# KHKT25.net
KiCad netlist of a schematic drawn in Altium Designer
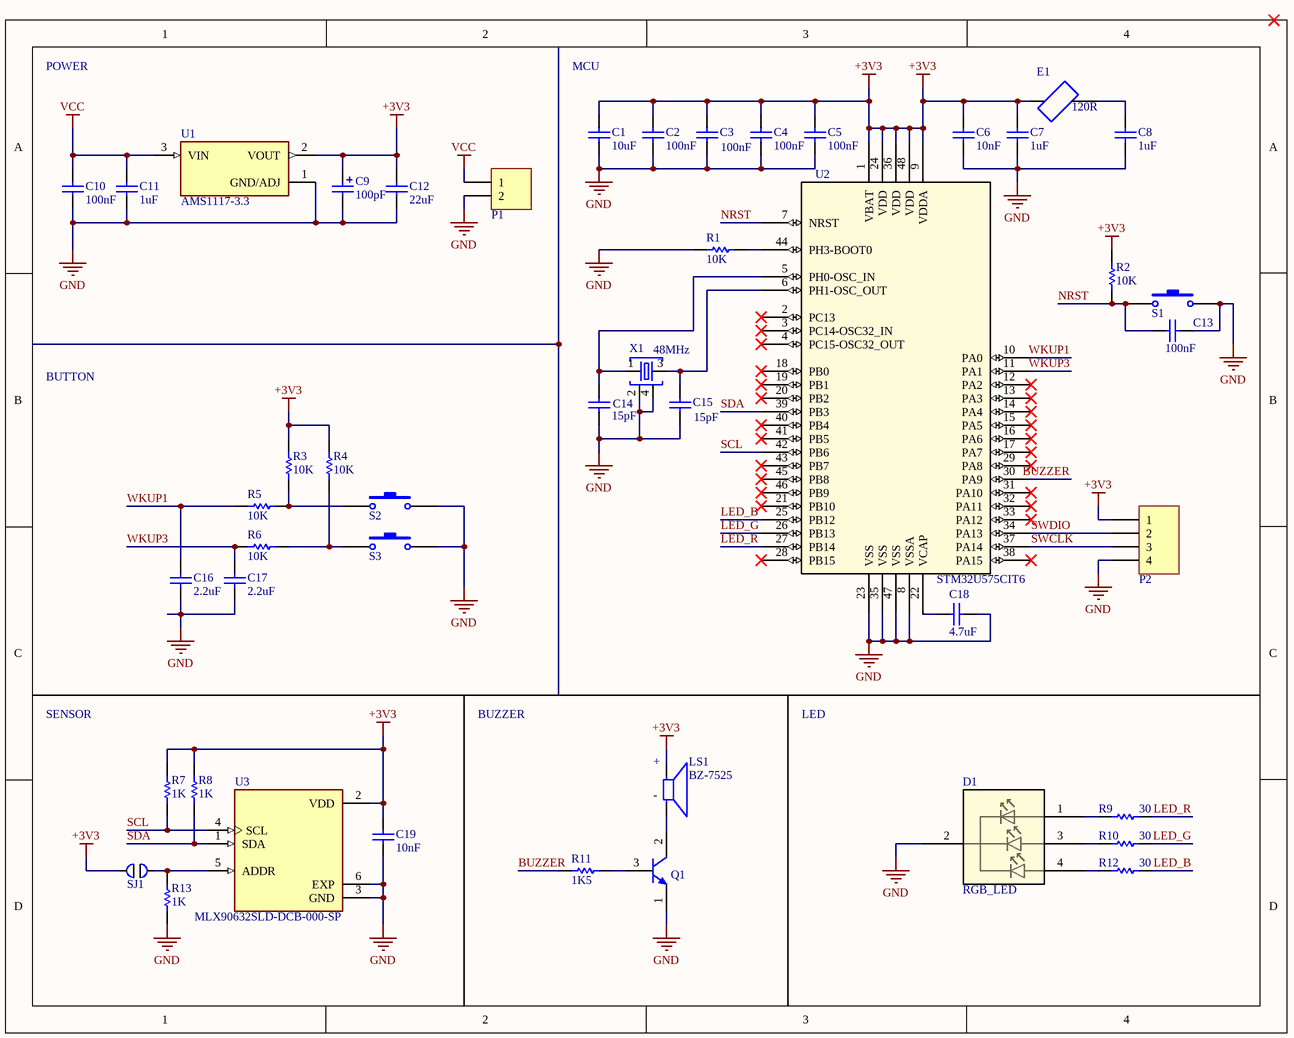
[diagram p0: KHKT25.SchDoc]

(export (version "E")
  (design (tool "Eeschema 10.0.6"))
  (components
    (comp (ref "C1")
      (value "10uF")
      (footprint "CAP-SM-0603")
      (description "Capacitor")
      (fields (field (name "Comment") "Cap Non-Pol SMD"))
      (libsource (lib "PIF_Library") (part "Cap Non-Pol SMD"))
    )
    (comp (ref "C2")
      (value "100nF")
      (footprint "CAP-SM-0603")
      (description "Capacitor")
      (fields (field (name "Comment") "Cap Non-Pol SMD"))
      (libsource (lib "PIF_Library") (part "Cap Non-Pol SMD"))
    )
    (comp (ref "C3")
      (value "100nF")
      (footprint "CAP-SM-0603")
      (description "Capacitor")
      (fields (field (name "Comment") "Cap Non-Pol SMD"))
      (libsource (lib "PIF_Library") (part "Cap Non-Pol SMD"))
    )
    (comp (ref "C4")
      (value "100nF")
      (footprint "CAP-SM-0603")
      (description "Capacitor")
      (fields (field (name "Comment") "Cap Non-Pol SMD"))
      (libsource (lib "PIF_Library") (part "Cap Non-Pol SMD"))
    )
    (comp (ref "C5")
      (value "100nF")
      (footprint "CAP-SM-0603")
      (description "Capacitor")
      (fields (field (name "Comment") "Cap Non-Pol SMD"))
      (libsource (lib "PIF_Library") (part "Cap Non-Pol SMD"))
    )
    (comp (ref "C6")
      (value "10nF")
      (footprint "CAP-SM-0603")
      (description "Capacitor")
      (fields (field (name "Comment") "Cap Non-Pol SMD"))
      (libsource (lib "PIF_Library") (part "Cap Non-Pol SMD"))
    )
    (comp (ref "C7")
      (value "1uF")
      (footprint "CAP-SM-0603")
      (description "Capacitor")
      (fields (field (name "Comment") "Cap Non-Pol SMD"))
      (libsource (lib "PIF_Library") (part "Cap Non-Pol SMD"))
    )
    (comp (ref "C8")
      (value "1uF")
      (footprint "CAP-SM-0603")
      (description "Capacitor")
      (fields (field (name "Comment") "Cap Non-Pol SMD"))
      (libsource (lib "PIF_Library") (part "Cap Non-Pol SMD"))
    )
    (comp (ref "C9")
      (value "100pF")
      (footprint "CAP ALU SIZE B")
      (description "Polarized Capacitor (Radial)")
      (fields (field (name "Comment") "Cap Pol SMD"))
      (libsource (lib "PIF_Library") (part "Cap Pol SMD"))
    )
    (comp (ref "C10")
      (value "100nF")
      (footprint "CAP-SM-0603")
      (description "Capacitor")
      (fields (field (name "Comment") "Cap Non-Pol SMD"))
      (libsource (lib "PIF_Library") (part "Cap Non-Pol SMD"))
    )
    (comp (ref "C11")
      (value "1uF")
      (footprint "CAP-SM-0603")
      (description "Capacitor")
      (fields (field (name "Comment") "Cap Non-Pol SMD"))
      (libsource (lib "PIF_Library") (part "Cap Non-Pol SMD"))
    )
    (comp (ref "C12")
      (value "22uF")
      (footprint "CAP-SM-0603")
      (description "Capacitor")
      (fields (field (name "Comment") "Cap Non-Pol SMD"))
      (libsource (lib "PIF_Library") (part "Cap Non-Pol SMD"))
    )
    (comp (ref "C13")
      (value "100nF")
      (footprint "CAP-SM-0603")
      (description "Capacitor")
      (fields (field (name "Comment") "Cap Non-Pol SMD"))
      (libsource (lib "PIF_Library") (part "Cap Non-Pol SMD"))
    )
    (comp (ref "C14")
      (value "15pF")
      (footprint "CAP-SM-0603")
      (description "Capacitor")
      (fields (field (name "Comment") "Cap Non-Pol SMD"))
      (libsource (lib "PIF_Library") (part "Cap Non-Pol SMD"))
    )
    (comp (ref "C15")
      (value "15pF")
      (footprint "CAP-SM-0603")
      (description "Capacitor")
      (fields (field (name "Comment") "Cap Non-Pol SMD"))
      (libsource (lib "PIF_Library") (part "Cap Non-Pol SMD"))
    )
    (comp (ref "C16")
      (value "2.2uF")
      (footprint "CAP-SM-0603")
      (description "Capacitor")
      (fields (field (name "Comment") "Cap Non-Pol SMD"))
      (libsource (lib "PIF_Library") (part "Cap Non-Pol SMD"))
    )
    (comp (ref "C17")
      (value "2.2uF")
      (footprint "CAP-SM-0603")
      (description "Capacitor")
      (fields (field (name "Comment") "Cap Non-Pol SMD"))
      (libsource (lib "PIF_Library") (part "Cap Non-Pol SMD"))
    )
    (comp (ref "C18")
      (value "4.7uF")
      (footprint "CAP-SM-0603")
      (description "Capacitor")
      (fields (field (name "Comment") "Cap Non-Pol SMD"))
      (libsource (lib "PIF_Library") (part "Cap Non-Pol SMD"))
    )
    (comp (ref "C19")
      (value "10nF")
      (footprint "CAP-SM-0603")
      (description "Capacitor")
      (fields (field (name "Comment") "Cap Non-Pol SMD"))
      (libsource (lib "PIF_Library") (part "Cap Non-Pol SMD"))
    )
    (comp (ref "D1")
      (value "RGB_LED")
      (footprint "RGB_LED")
      (description "Description")
      (fields
        (field (name "MANUFACTURER_PART_NUMBER") "L-154A4SURKQBDZGW")
        (field (name "COPYRIGHT") "Copyright (C) 2025 Ultra Librarian. All rights reserved.")
      )
      (libsource (lib "IntLib") (part "RGB_LED"))
    )
    (comp (ref "E1")
      (value "120R")
      (footprint "FB_MI0805K400R-10")
      (fields (field (name "MF") "Laird-Signal Integrity Products") (field (name "MP") "MI0805K400R-10"))
      (libsource (lib "IntLib") (part "MI0805K400R-10"))
    )
    (comp (ref "LS1")
      (value "BZ-7525")
      (footprint "XDCCMT-7525")
      (description "7.5 mm, 3.6 Vo-p, 80 dB, Surface Mount (SMT), Magnetic Audio Transducer Buzzer")
      (fields (field (name "MF") "Same Sky") (field (name "MP") "CMT-7525-80-SMT-TR"))
      (libsource (lib "IntLib") (part "BZ-7525"))
    )
    (comp (ref "P1")
      (value "Header 2")
      (footprint "JP2")
      (description "Header, 2-Pin")
      (fields (field (name "PUBLISHER") "Altium Limited"))
      (libsource (lib "PIF_Library") (part "Header 2"))
    )
    (comp (ref "P2")
      (value "Header 4H")
      (footprint "JP4H")
      (description "Header, 4-Pin, Right Angle")
      (fields (field (name "PUBLISHER") "Altium Limited"))
      (libsource (lib "PIF_Library") (part "Header 4H"))
    )
    (comp (ref "Q1")
      (value "C1815")
      (footprint "QTO-92")
      (description "NPN Bipolar Transistor")
      (libsource (lib "PIF_Library") (part "C1815"))
    )
    (comp (ref "R1")
      (value "10K")
      (footprint "RES-SM-0603")
      (description "Resistor")
      (fields (field (name "Comment") "RESISTOR SMD"))
      (libsource (lib "PIF_Library") (part "RESISTOR SMD"))
    )
    (comp (ref "R2")
      (value "10K")
      (footprint "RES-SM-0603")
      (description "Resistor")
      (fields (field (name "Comment") "RESISTOR SMD"))
      (libsource (lib "PIF_Library") (part "RESISTOR SMD"))
    )
    (comp (ref "R3")
      (value "10K")
      (footprint "RES-SM-0603")
      (description "Resistor")
      (fields (field (name "Comment") "RESISTOR SMD"))
      (libsource (lib "PIF_Library") (part "RESISTOR SMD"))
    )
    (comp (ref "R4")
      (value "10K")
      (footprint "RES-SM-0603")
      (description "Resistor")
      (fields (field (name "Comment") "RESISTOR SMD"))
      (libsource (lib "PIF_Library") (part "RESISTOR SMD"))
    )
    (comp (ref "R5")
      (value "10K")
      (footprint "RES-SM-0603")
      (description "Resistor")
      (fields (field (name "Comment") "RESISTOR SMD"))
      (libsource (lib "PIF_Library") (part "RESISTOR SMD"))
    )
    (comp (ref "R6")
      (value "10K")
      (footprint "RES-SM-0603")
      (description "Resistor")
      (fields (field (name "Comment") "RESISTOR SMD"))
      (libsource (lib "PIF_Library") (part "RESISTOR SMD"))
    )
    (comp (ref "R7")
      (value "1K")
      (footprint "RES-SM-0603")
      (description "Resistor")
      (fields (field (name "Comment") "RESISTOR SMD"))
      (libsource (lib "PIF_Library") (part "RESISTOR SMD"))
    )
    (comp (ref "R8")
      (value "1K")
      (footprint "RES-SM-0603")
      (description "Resistor")
      (fields (field (name "Comment") "RESISTOR SMD"))
      (libsource (lib "PIF_Library") (part "RESISTOR SMD"))
    )
    (comp (ref "R9")
      (value "30")
      (footprint "RES-SM-0603")
      (description "Resistor")
      (fields (field (name "Comment") "RESISTOR SMD"))
      (libsource (lib "PIF_Library") (part "RESISTOR SMD"))
    )
    (comp (ref "R10")
      (value "30")
      (footprint "RES-SM-0603")
      (description "Resistor")
      (fields (field (name "Comment") "RESISTOR SMD"))
      (libsource (lib "PIF_Library") (part "RESISTOR SMD"))
    )
    (comp (ref "R11")
      (value "1K5")
      (footprint "RES-SM-0603")
      (description "Resistor")
      (fields (field (name "Comment") "RESISTOR SMD"))
      (libsource (lib "PIF_Library") (part "RESISTOR SMD"))
    )
    (comp (ref "R12")
      (value "30")
      (footprint "RES-SM-0603")
      (description "Resistor")
      (fields (field (name "Comment") "RESISTOR SMD"))
      (libsource (lib "PIF_Library") (part "RESISTOR SMD"))
    )
    (comp (ref "R13")
      (value "1K")
      (footprint "RES-SM-0603")
      (description "Resistor")
      (fields (field (name "Comment") "RESISTOR SMD"))
      (libsource (lib "PIF_Library") (part "RESISTOR SMD"))
    )
    (comp (ref "S1")
      (value "Tact SW - 2Pin")
      (footprint "SW_SMD")
      (description "Switch button 2 pin")
      (libsource (lib "PIF_Library") (part "Tact SW - 2Pin"))
    )
    (comp (ref "S2")
      (value "Tact SW - 2Pin")
      (footprint "SW_SMD")
      (description "Switch button 2 pin")
      (libsource (lib "PIF_Library") (part "Tact SW - 2Pin"))
    )
    (comp (ref "S3")
      (value "Tact SW - 2Pin")
      (footprint "SW_SMD")
      (description "Switch button 2 pin")
      (libsource (lib "PIF_Library") (part "Tact SW - 2Pin"))
    )
    (comp (ref "SJ1") (value "Solder jumper") (footprint "SJ") (libsource (lib "IntLib") (part "SJ")))
    (comp (ref "U1")
      (value "AMS1117-3.3")
      (footprint "SOT229P700X180-4N")
      (description "Sot223/Pkg 1-Amp 3.3-Volt Low Drop Out Voltage Regulatator")
      (fields (field (name "MF") "Advanced Monolithic Systems"))
      (libsource (lib "IntLib") (part "AMS1117-3.3"))
    )
    (comp (ref "U2")
      (value "STM32U575CIT6")
      (footprint "LQFP48-7x7mm_STM")
      (description "Ultra-low-power with FPU Arm Cortex-M33 MCU with TrustZone, 160 MHz with 2 Mbytes of Flash memory")
      (fields (field (name "COPYRIGHT") "Copyright (C) 2025 Ultra Librarian. All rights reserved."))
      (libsource (lib "IntLib") (part "STM32U575CIT6"))
    )
    (comp (ref "U3")
      (value "MLX90632SLD-DCB-000-SP")
      (footprint "MLX90632")
      (fields (field (name "MP") "MLX90632SLD-BCB-000-SP"))
      (libsource (lib "IntLib") (part "MLX90632SLD-BCB-000-SP"))
    )
    (comp (ref "X1")
      (value "48MHz")
      (footprint "TSX-3225")
      (description "Crystal")
      (fields (field (name "MF") "EPSON") (field (name "MP") "TSX-3225"))
      (libsource (lib "IntLib") (part "TSX-3225"))
    )
  )
  (nets
    (net (code "1") (name "+3V3") (class "Default")
      (node (ref "C1") (pin "2") (pinfunction "2_2") (pintype "passive"))
      (node (ref "C12") (pin "2") (pinfunction "2_2") (pintype "passive"))
      (node (ref "C19") (pin "2") (pinfunction "2_2") (pintype "passive"))
      (node (ref "C2") (pin "2") (pinfunction "2_2") (pintype "passive"))
      (node (ref "C3") (pin "2") (pinfunction "2_2") (pintype "passive"))
      (node (ref "C4") (pin "2") (pinfunction "2_2") (pintype "passive"))
      (node (ref "C5") (pin "2") (pinfunction "2_2") (pintype "passive"))
      (node (ref "C6") (pin "2") (pinfunction "2_2") (pintype "passive"))
      (node (ref "C7") (pin "2") (pinfunction "2_2") (pintype "passive"))
      (node (ref "C9") (pin "1") (pinfunction "1_1") (pintype "passive"))
      (node (ref "E1") (pin "1") (pinfunction "1_1") (pintype "passive"))
      (node (ref "LS1") (pin "P") (pinfunction "P_P") (pintype "passive"))
      (node (ref "P2") (pin "1") (pinfunction "1_1") (pintype "passive"))
      (node (ref "R2") (pin "1") (pinfunction "1_1") (pintype "passive"))
      (node (ref "R3") (pin "1") (pinfunction "1_1") (pintype "passive"))
      (node (ref "R4") (pin "1") (pinfunction "1_1") (pintype "passive"))
      (node (ref "R7") (pin "1") (pinfunction "1_1") (pintype "passive"))
      (node (ref "R8") (pin "1") (pinfunction "1_1") (pintype "passive"))
      (node (ref "SJ1") (pin "1") (pinfunction "1_1") (pintype "power_in"))
      (node (ref "U1") (pin "2") (pinfunction "VOUT_2") (pintype "output"))
      (node (ref "U2") (pin "1") (pinfunction "VBAT_1") (pintype "power_in"))
      (node (ref "U2") (pin "24") (pinfunction "VDD_24") (pintype "power_in"))
      (node (ref "U2") (pin "36") (pinfunction "VDD_36") (pintype "power_in"))
      (node (ref "U2") (pin "48") (pinfunction "VDD_48") (pintype "power_in"))
      (node (ref "U2") (pin "9") (pinfunction "VDDA_9") (pintype "power_in"))
      (node (ref "U3") (pin "2") (pinfunction "VDD_2") (pintype "power_in"))
    )
    (net (code "2") (name "/BUZZER") (class "Default")
      (node (ref "R11") (pin "1") (pinfunction "1_1") (pintype "passive"))
      (node (ref "U2") (pin "30") (pinfunction "PA9_30") (pintype "bidirectional"))
    )
    (net (code "3") (name "/LED_B") (class "Default")
      (node (ref "R12") (pin "1") (pinfunction "1_1") (pintype "passive"))
      (node (ref "U2") (pin "25") (pinfunction "PB12_25") (pintype "bidirectional"))
    )
    (net (code "4") (name "/LED_G") (class "Default")
      (node (ref "R10") (pin "1") (pinfunction "1_1") (pintype "passive"))
      (node (ref "U2") (pin "26") (pinfunction "PB13_26") (pintype "bidirectional"))
    )
    (net (code "5") (name "/LED_R") (class "Default")
      (node (ref "R9") (pin "1") (pinfunction "1_1") (pintype "passive"))
      (node (ref "U2") (pin "27") (pinfunction "PB14_27") (pintype "bidirectional"))
    )
    (net (code "6") (name "/NRST") (class "Default")
      (node (ref "C13") (pin "1") (pinfunction "1_1") (pintype "passive"))
      (node (ref "R2") (pin "2") (pinfunction "2_2") (pintype "passive"))
      (node (ref "S1") (pin "1") (pinfunction "1_1") (pintype "passive"))
      (node (ref "U2") (pin "7") (pinfunction "NRST_7") (pintype "bidirectional"))
    )
    (net (code "7") (name "/SCL") (class "Default")
      (node (ref "R7") (pin "2") (pinfunction "2_2") (pintype "passive"))
      (node (ref "U2") (pin "42") (pinfunction "PB6_42") (pintype "bidirectional"))
      (node (ref "U3") (pin "4") (pinfunction "SCL_4") (pintype "input"))
    )
    (net (code "8") (name "/SDA") (class "Default")
      (node (ref "R8") (pin "2") (pinfunction "2_2") (pintype "passive"))
      (node (ref "U2") (pin "39") (pinfunction "PB3_39") (pintype "bidirectional"))
      (node (ref "U3") (pin "1") (pinfunction "SDA_1") (pintype "input"))
    )
    (net (code "9") (name "/SWCLK") (class "Default")
      (node (ref "P2") (pin "3") (pinfunction "3_3") (pintype "passive"))
      (node (ref "U2") (pin "37") (pinfunction "PA14_37") (pintype "bidirectional"))
    )
    (net (code "10") (name "/SWDIO") (class "Default")
      (node (ref "P2") (pin "2") (pinfunction "2_2") (pintype "passive"))
      (node (ref "U2") (pin "34") (pinfunction "PA13_34") (pintype "bidirectional"))
    )
    (net (code "11") (name "/WKUP1") (class "Default")
      (node (ref "C16") (pin "2") (pinfunction "2_2") (pintype "passive"))
      (node (ref "R5") (pin "1") (pinfunction "1_1") (pintype "passive"))
      (node (ref "U2") (pin "10") (pinfunction "PA0_10") (pintype "bidirectional"))
    )
    (net (code "12") (name "/WKUP3") (class "Default")
      (node (ref "C17") (pin "2") (pinfunction "2_2") (pintype "passive"))
      (node (ref "R6") (pin "1") (pinfunction "1_1") (pintype "passive"))
      (node (ref "U2") (pin "11") (pinfunction "PA1_11") (pintype "bidirectional"))
    )
    (net (code "13") (name "GND") (class "Default")
      (node (ref "C1") (pin "1") (pinfunction "1_1") (pintype "passive"))
      (node (ref "C10") (pin "1") (pinfunction "1_1") (pintype "passive"))
      (node (ref "C11") (pin "1") (pinfunction "1_1") (pintype "passive"))
      (node (ref "C12") (pin "1") (pinfunction "1_1") (pintype "passive"))
      (node (ref "C13") (pin "2") (pinfunction "2_2") (pintype "passive"))
      (node (ref "C14") (pin "1") (pinfunction "1_1") (pintype "passive"))
      (node (ref "C15") (pin "1") (pinfunction "1_1") (pintype "passive"))
      (node (ref "C16") (pin "1") (pinfunction "1_1") (pintype "passive"))
      (node (ref "C17") (pin "1") (pinfunction "1_1") (pintype "passive"))
      (node (ref "C18") (pin "1") (pinfunction "1_1") (pintype "passive"))
      (node (ref "C19") (pin "1") (pinfunction "1_1") (pintype "passive"))
      (node (ref "C2") (pin "1") (pinfunction "1_1") (pintype "passive"))
      (node (ref "C3") (pin "1") (pinfunction "1_1") (pintype "passive"))
      (node (ref "C4") (pin "1") (pinfunction "1_1") (pintype "passive"))
      (node (ref "C5") (pin "1") (pinfunction "1_1") (pintype "passive"))
      (node (ref "C6") (pin "1") (pinfunction "1_1") (pintype "passive"))
      (node (ref "C7") (pin "1") (pinfunction "1_1") (pintype "passive"))
      (node (ref "C8") (pin "1") (pinfunction "1_1") (pintype "passive"))
      (node (ref "C9") (pin "2") (pinfunction "2_2") (pintype "passive"))
      (node (ref "D1") (pin "2") (pinfunction "2_2") (pintype "passive"))
      (node (ref "P1") (pin "2") (pinfunction "2_2") (pintype "passive"))
      (node (ref "P2") (pin "4") (pinfunction "4_4") (pintype "passive"))
      (node (ref "Q1") (pin "1") (pinfunction "E_1") (pintype "passive"))
      (node (ref "R1") (pin "2") (pinfunction "2_2") (pintype "passive"))
      (node (ref "R13") (pin "2") (pinfunction "2_2") (pintype "passive"))
      (node (ref "S1") (pin "2") (pinfunction "2_2") (pintype "passive"))
      (node (ref "S2") (pin "2") (pinfunction "2_2") (pintype "passive"))
      (node (ref "S3") (pin "2") (pinfunction "2_2") (pintype "passive"))
      (node (ref "U1") (pin "1") (pinfunction "GND/ADJ_1") (pintype "power_in"))
      (node (ref "U2") (pin "23") (pinfunction "VSS_23") (pintype "power_in"))
      (node (ref "U2") (pin "35") (pinfunction "VSS_35") (pintype "power_in"))
      (node (ref "U2") (pin "47") (pinfunction "VSS_47") (pintype "power_in"))
      (node (ref "U2") (pin "8") (pinfunction "VSSA_8") (pintype "power_in"))
      (node (ref "U3") (pin "3") (pinfunction "GND_3") (pintype "power_in"))
      (node (ref "U3") (pin "6") (pinfunction "EXP_6") (pintype "power_in"))
      (node (ref "X1") (pin "2") (pinfunction "2_2") (pintype "passive"))
      (node (ref "X1") (pin "4") (pinfunction "4_4") (pintype "passive"))
    )
    (net (code "14") (name "Net-(C8-Pad2)") (class "Default")
      (node (ref "C8") (pin "2") (pinfunction "2_2") (pintype "passive"))
      (node (ref "E1") (pin "2") (pinfunction "2_2") (pintype "passive"))
    )
    (net (code "15") (name "Net-(D1-Pad1)") (class "Default")
      (node (ref "D1") (pin "1") (pinfunction "1_1") (pintype "passive"))
      (node (ref "R9") (pin "2") (pinfunction "2_2") (pintype "passive"))
    )
    (net (code "16") (name "Net-(D1-Pad3)") (class "Default")
      (node (ref "D1") (pin "3") (pinfunction "3_3") (pintype "passive"))
      (node (ref "R10") (pin "2") (pinfunction "2_2") (pintype "passive"))
    )
    (net (code "17") (name "Net-(D1-Pad4)") (class "Default")
      (node (ref "D1") (pin "4") (pinfunction "4_4") (pintype "passive"))
      (node (ref "R12") (pin "2") (pinfunction "2_2") (pintype "passive"))
    )
    (net (code "18") (name "Net-(Q1-B)") (class "Default")
      (node (ref "Q1") (pin "3") (pinfunction "B_3") (pintype "passive"))
      (node (ref "R11") (pin "2") (pinfunction "2_2") (pintype "passive"))
    )
    (net (code "19") (name "Net-(Q1-C)") (class "Default")
      (node (ref "LS1") (pin "N") (pinfunction "N_N") (pintype "passive"))
      (node (ref "Q1") (pin "2") (pinfunction "C_2") (pintype "passive"))
    )
    (net (code "20") (name "Net-(R3-Pad2)") (class "Default")
      (node (ref "R3") (pin "2") (pinfunction "2_2") (pintype "passive"))
      (node (ref "R5") (pin "2") (pinfunction "2_2") (pintype "passive"))
      (node (ref "S2") (pin "1") (pinfunction "1_1") (pintype "passive"))
    )
    (net (code "21") (name "Net-(R4-Pad2)") (class "Default")
      (node (ref "R4") (pin "2") (pinfunction "2_2") (pintype "passive"))
      (node (ref "R6") (pin "2") (pinfunction "2_2") (pintype "passive"))
      (node (ref "S3") (pin "1") (pinfunction "1_1") (pintype "passive"))
    )
    (net (code "22") (name "Net-(U2-PH0-OSC_IN)") (class "Default")
      (node (ref "C14") (pin "2") (pinfunction "2_2") (pintype "passive"))
      (node (ref "U2") (pin "5") (pinfunction "PH0-OSC_IN_5") (pintype "bidirectional"))
      (node (ref "X1") (pin "1") (pinfunction "1_1") (pintype "passive"))
    )
    (net (code "23") (name "Net-(U2-PH1-OSC_OUT)") (class "Default")
      (node (ref "C15") (pin "2") (pinfunction "2_2") (pintype "passive"))
      (node (ref "U2") (pin "6") (pinfunction "PH1-OSC_OUT_6") (pintype "bidirectional"))
      (node (ref "X1") (pin "3") (pinfunction "3_3") (pintype "passive"))
    )
    (net (code "24") (name "Net-(U2-PH3-BOOT0)") (class "Default")
      (node (ref "R1") (pin "1") (pinfunction "1_1") (pintype "passive"))
      (node (ref "U2") (pin "44") (pinfunction "PH3-BOOT0_44") (pintype "bidirectional"))
    )
    (net (code "25") (name "Net-(U2-VCAP)") (class "Default")
      (node (ref "C18") (pin "2") (pinfunction "2_2") (pintype "passive"))
      (node (ref "U2") (pin "22") (pinfunction "VCAP_22") (pintype "power_in"))
    )
    (net (code "26") (name "Net-(U3-ADDR)") (class "Default")
      (node (ref "R13") (pin "1") (pinfunction "1_1") (pintype "passive"))
      (node (ref "SJ1") (pin "1") (pinfunction "1_1") (pintype "power_in"))
      (node (ref "U3") (pin "5") (pinfunction "ADDR_5") (pintype "input"))
    )
    (net (code "27") (name "VCC") (class "Default")
      (node (ref "C10") (pin "2") (pinfunction "2_2") (pintype "passive"))
      (node (ref "C11") (pin "2") (pinfunction "2_2") (pintype "passive"))
      (node (ref "P1") (pin "1") (pinfunction "1_1") (pintype "passive"))
      (node (ref "U1") (pin "3") (pinfunction "VIN_3") (pintype "input"))
    )
    (net (code "28") (name "unconnected-(U2-PA2-Pad12)") (class "Default")
      (node (ref "U2") (pin "12") (pinfunction "PA2_12") (pintype "bidirectional+no_connect"))
    )
    (net (code "29") (name "unconnected-(U2-PA3-Pad13)") (class "Default")
      (node (ref "U2") (pin "13") (pinfunction "PA3_13") (pintype "bidirectional+no_connect"))
    )
    (net (code "30") (name "unconnected-(U2-PA4-Pad14)") (class "Default")
      (node (ref "U2") (pin "14") (pinfunction "PA4_14") (pintype "bidirectional+no_connect"))
    )
    (net (code "31") (name "unconnected-(U2-PA5-Pad15)") (class "Default")
      (node (ref "U2") (pin "15") (pinfunction "PA5_15") (pintype "bidirectional+no_connect"))
    )
    (net (code "32") (name "unconnected-(U2-PA6-Pad16)") (class "Default")
      (node (ref "U2") (pin "16") (pinfunction "PA6_16") (pintype "bidirectional+no_connect"))
    )
    (net (code "33") (name "unconnected-(U2-PA7-Pad17)") (class "Default")
      (node (ref "U2") (pin "17") (pinfunction "PA7_17") (pintype "bidirectional+no_connect"))
    )
    (net (code "34") (name "unconnected-(U2-PA8-Pad29)") (class "Default")
      (node (ref "U2") (pin "29") (pinfunction "PA8_29") (pintype "bidirectional+no_connect"))
    )
    (net (code "35") (name "unconnected-(U2-PA10-Pad31)") (class "Default")
      (node (ref "U2") (pin "31") (pinfunction "PA10_31") (pintype "bidirectional+no_connect"))
    )
    (net (code "36") (name "unconnected-(U2-PA11-Pad32)") (class "Default")
      (node (ref "U2") (pin "32") (pinfunction "PA11_32") (pintype "bidirectional+no_connect"))
    )
    (net (code "37") (name "unconnected-(U2-PA12-Pad33)") (class "Default")
      (node (ref "U2") (pin "33") (pinfunction "PA12_33") (pintype "bidirectional+no_connect"))
    )
    (net (code "38") (name "unconnected-(U2-PA15-Pad38)") (class "Default")
      (node (ref "U2") (pin "38") (pinfunction "PA15_38") (pintype "bidirectional+no_connect"))
    )
    (net (code "39") (name "unconnected-(U2-PB0-Pad18)") (class "Default")
      (node (ref "U2") (pin "18") (pinfunction "PB0_18") (pintype "bidirectional+no_connect"))
    )
    (net (code "40") (name "unconnected-(U2-PB1-Pad19)") (class "Default")
      (node (ref "U2") (pin "19") (pinfunction "PB1_19") (pintype "bidirectional+no_connect"))
    )
    (net (code "41") (name "unconnected-(U2-PB2-Pad20)") (class "Default")
      (node (ref "U2") (pin "20") (pinfunction "PB2_20") (pintype "bidirectional+no_connect"))
    )
    (net (code "42") (name "unconnected-(U2-PB4-Pad40)") (class "Default")
      (node (ref "U2") (pin "40") (pinfunction "PB4_40") (pintype "bidirectional+no_connect"))
    )
    (net (code "43") (name "unconnected-(U2-PB5-Pad41)") (class "Default")
      (node (ref "U2") (pin "41") (pinfunction "PB5_41") (pintype "bidirectional+no_connect"))
    )
    (net (code "44") (name "unconnected-(U2-PB7-Pad43)") (class "Default")
      (node (ref "U2") (pin "43") (pinfunction "PB7_43") (pintype "bidirectional+no_connect"))
    )
    (net (code "45") (name "unconnected-(U2-PB8-Pad45)") (class "Default")
      (node (ref "U2") (pin "45") (pinfunction "PB8_45") (pintype "bidirectional+no_connect"))
    )
    (net (code "46") (name "unconnected-(U2-PB9-Pad46)") (class "Default")
      (node (ref "U2") (pin "46") (pinfunction "PB9_46") (pintype "bidirectional+no_connect"))
    )
    (net (code "47") (name "unconnected-(U2-PB10-Pad21)") (class "Default")
      (node (ref "U2") (pin "21") (pinfunction "PB10_21") (pintype "bidirectional+no_connect"))
    )
    (net (code "48") (name "unconnected-(U2-PB15-Pad28)") (class "Default")
      (node (ref "U2") (pin "28") (pinfunction "PB15_28") (pintype "bidirectional+no_connect"))
    )
    (net (code "49") (name "unconnected-(U2-PC13-Pad2)") (class "Default")
      (node (ref "U2") (pin "2") (pinfunction "PC13_2") (pintype "bidirectional+no_connect"))
    )
    (net (code "50") (name "unconnected-(U2-PC14-OSC32_IN-Pad3)") (class "Default")
      (node (ref "U2") (pin "3") (pinfunction "PC14-OSC32_IN_3") (pintype "bidirectional+no_connect"))
    )
    (net (code "51") (name "unconnected-(U2-PC15-OSC32_OUT-Pad4)") (class "Default")
      (node (ref "U2") (pin "4") (pinfunction "PC15-OSC32_OUT_4") (pintype "bidirectional+no_connect"))
    )
  )
)
